# Voeding.net
KiCad netlist of a schematic drawn in Altium Designer
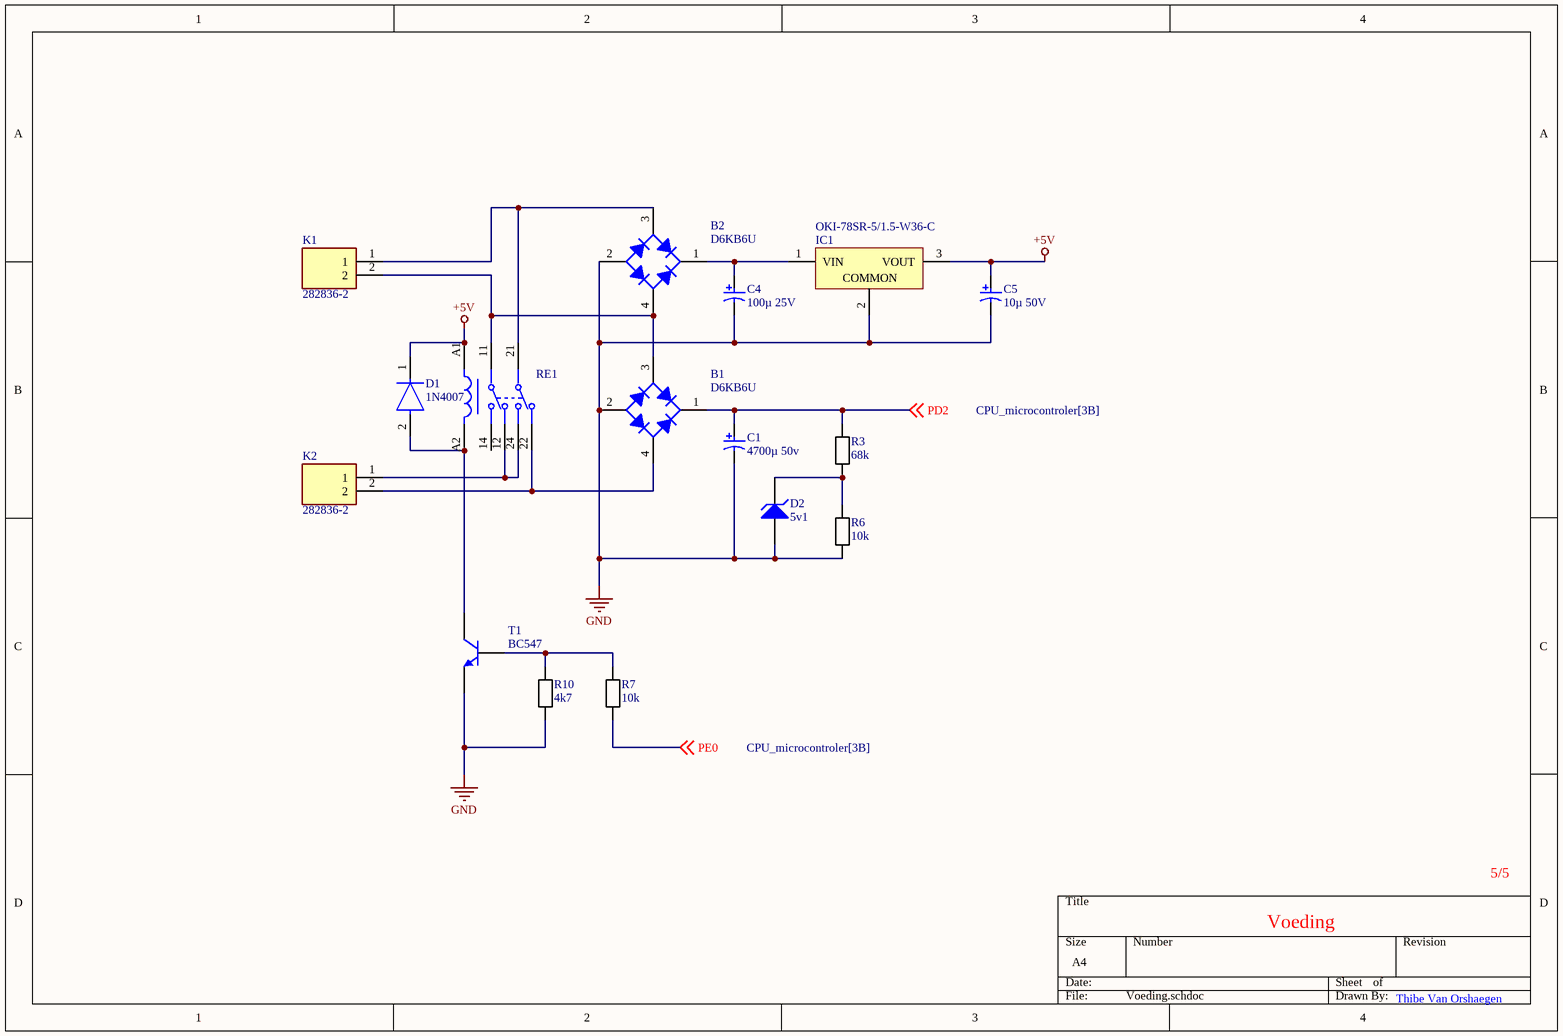
[diagram p0: Voeding.schdoc]

(export (version "E")
  (design (tool "Eeschema 10.0.6"))
  (components
    (comp (ref "B1")
      (value "D6KB6U")
      (footprint "ttf")
      (fields (field (name "MANUFACTURER") "Diodes Inc"))
      (libsource (lib "Soldeerstation") (part "Bridge_Rectifier"))
    )
    (comp (ref "B2")
      (value "D6KB6U")
      (footprint "ttf")
      (fields (field (name "MANUFACTURER") "Diodes Inc"))
      (libsource (lib "Soldeerstation") (part "Bridge_Rectifier"))
    )
    (comp (ref "C1")
      (value "4700µ 50v")
      (footprint "CE_D25_L25_plugin")
      (fields (field (name "MANUFACTURER") "Panasonic"))
      (libsource (lib "Soldeerstation") (part "Capacitor_Electrolytic"))
    )
    (comp (ref "C4")
      (value "100µ 25V")
      (footprint "CE_D8_L10")
      (fields (field (name "MANUFACTURER") "Panasonic"))
      (libsource (lib "Soldeerstation") (part "Capacitor_Electrolytic"))
    )
    (comp (ref "C5")
      (value "10µ 50V")
      (footprint "CE_D8_L10")
      (fields (field (name "MANUFACTURER") "Panasonic"))
      (libsource (lib "Soldeerstation") (part "Capacitor_Electrolytic"))
    )
    (comp (ref "D1")
      (value "1N4007")
      (footprint "SOD-123FL")
      (fields
        (field (name "MANUFACTURER") "Diotec")
        (field (name "OCTOPART") "https://octopart.com/1n4007-diotec-4040411")
      )
      (libsource (lib "Soldeerstation") (part "Diode"))
    )
    (comp (ref "D2")
      (value "5v1")
      (footprint "SOD-123FL")
      (fields (field (name "MANUFACTURER") "On Semiconductor") (field (name "PARTNUMBER") "1SMB5920BT3G"))
      (libsource (lib "Soldeerstation") (part "Zener_Diode"))
    )
    (comp (ref "IC1")
      (value "OKI-78SR-5/1.5-W36-C")
      (footprint "OKI78SR515W36C")
      (fields (field (name "MANUFACTURER") "Murata"))
      (libsource (lib "Soldeerstation") (part "DC/DC Converter"))
    )
    (comp (ref "K1")
      (value "282836-2")
      (footprint "PcbLib3:Schroefconnector 2 Pin")
      (description "Connector")
      (libsource (lib "Soldeerstation") (part "Schroefconnector 2 Pin L"))
    )
    (comp (ref "K2")
      (value "282836-2")
      (footprint "PcbLib3:Schroefconnector 2 Pin")
      (description "Connector")
      (libsource (lib "Soldeerstation") (part "Schroefconnector 2 Pin L"))
    )
    (comp (ref "R3")
      (value "68k")
      (footprint "RESC2013X50X30ML20T20")
      (fields (field (name "MANUFACTURER") "Vishay Dale") (field (name "PART NUMBER") "CRCW08050000Z0EA"))
      (libsource (lib "Soldeerstation") (part "Weerstand"))
    )
    (comp (ref "R6")
      (value "10k")
      (footprint "RESC2013X50X30ML20T20")
      (fields (field (name "MANUFACTURER") "Vishay Dale") (field (name "PART NUMBER") "CRCW08050000Z0EA"))
      (libsource (lib "Soldeerstation") (part "Weerstand"))
    )
    (comp (ref "R7")
      (value "10k")
      (footprint "RESC2013X50X30ML20T20")
      (fields (field (name "MANUFACTURER") "Vishay Dale") (field (name "PART NUMBER") "CRCW08050000Z0EA"))
      (libsource (lib "Soldeerstation") (part "Weerstand"))
    )
    (comp (ref "R10")
      (value "4k7")
      (footprint "RESC2013X50X30ML20T20")
      (fields (field (name "MANUFACTURER") "Vishay Dale") (field (name "PART NUMBER") "CRCW08050000Z0EA"))
      (libsource (lib "Soldeerstation") (part "Weerstand"))
    )
    (comp (ref "RE1")
      (value "~")
      (footprint "RT42")
      (fields
        (field (name "MANUFACTURER PART NUMBER") "RT424005")
        (field (name "OCTOPART") "https://octopart.com/5-1393243-9-te+connectivity-41835766")
        (field (name "MANUFACTURER") "TE Connectivity")
      )
      (libsource (lib "Soldeerstation") (part "RELAY_GENERAL_PURPOSE"))
    )
    (comp (ref "T1")
      (value "BC547")
      (footprint "SOT_23")
      (fields (field (name "MANUFACTURER") "On Semiconductor") (field (name "PARTNUMBER") "BC547C"))
      (libsource (lib "Soldeerstation") (part "Transistor_NPN"))
    )
  )
  (nets
    (net (code "1") (name "+5V") (class "Default")
      (node (ref "C5") (pin "2") (pinfunction "2_2") (pintype "passive"))
      (node (ref "D1") (pin "1") (pinfunction "C_1") (pintype "passive"))
      (node (ref "IC1") (pin "3") (pinfunction "VOUT_3") (pintype "power_in"))
      (node (ref "RE1") (pin "A1") (pinfunction "A1_A1") (pintype "passive"))
    )
    (net (code "2") (name "GND") (class "Default")
      (node (ref "B1") (pin "2") (pinfunction "A_2") (pintype "passive"))
      (node (ref "B2") (pin "2") (pinfunction "A_2") (pintype "passive"))
      (node (ref "C1") (pin "1") (pinfunction "1_1") (pintype "passive"))
      (node (ref "C4") (pin "1") (pinfunction "1_1") (pintype "passive"))
      (node (ref "C5") (pin "1") (pinfunction "1_1") (pintype "passive"))
      (node (ref "D2") (pin "2") (pinfunction "A_2") (pintype "passive"))
      (node (ref "IC1") (pin "2") (pinfunction "COMMON_2") (pintype "power_in"))
      (node (ref "R10") (pin "1") (pinfunction "1_1") (pintype "passive"))
      (node (ref "R6") (pin "1") (pinfunction "1_1") (pintype "passive"))
      (node (ref "T1") (pin "3") (pinfunction "E_3") (pintype "passive"))
    )
    (net (code "3") (name "Net-(B1-C-Pad3)") (class "Default")
      (node (ref "B1") (pin "3") (pinfunction "C_3") (pintype "passive"))
      (node (ref "B2") (pin "4") (pinfunction "C_4") (pintype "passive"))
      (node (ref "K1") (pin "2") (pinfunction "2_2") (pintype "passive"))
      (node (ref "RE1") (pin "11") (pinfunction "11_11") (pintype "passive"))
    )
    (net (code "4") (name "Net-(B1-C-Pad4)") (class "Default")
      (node (ref "B1") (pin "4") (pinfunction "C_4") (pintype "passive"))
      (node (ref "K2") (pin "2") (pinfunction "2_2") (pintype "passive"))
      (node (ref "RE1") (pin "22") (pinfunction "22_22") (pintype "passive"))
    )
    (net (code "5") (name "Net-(B2-C-Pad3)") (class "Default")
      (node (ref "B2") (pin "3") (pinfunction "C_3") (pintype "passive"))
      (node (ref "K1") (pin "1") (pinfunction "1_1") (pintype "passive"))
      (node (ref "RE1") (pin "21") (pinfunction "21_21") (pintype "passive"))
    )
    (net (code "6") (name "Net-(B2-K)") (class "Default")
      (node (ref "B2") (pin "1") (pinfunction "K_1") (pintype "passive"))
      (node (ref "C4") (pin "2") (pinfunction "2_2") (pintype "passive"))
      (node (ref "IC1") (pin "1") (pinfunction "VIN_1") (pintype "power_in"))
    )
    (net (code "7") (name "Net-(D1-A)") (class "Default")
      (node (ref "D1") (pin "2") (pinfunction "A_2") (pintype "passive"))
      (node (ref "RE1") (pin "A2") (pinfunction "A2_A2") (pintype "passive"))
      (node (ref "T1") (pin "1") (pinfunction "C_1") (pintype "passive"))
    )
    (net (code "8") (name "Net-(D2-K)") (class "Default")
      (node (ref "D2") (pin "1") (pinfunction "K_1") (pintype "passive"))
      (node (ref "R3") (pin "1") (pinfunction "1_1") (pintype "passive"))
      (node (ref "R6") (pin "2") (pinfunction "2_2") (pintype "passive"))
    )
    (net (code "9") (name "Net-(K2-Pad1)") (class "Default")
      (node (ref "K2") (pin "1") (pinfunction "1_1") (pintype "passive"))
      (node (ref "RE1") (pin "12") (pinfunction "12_12") (pintype "passive"))
      (node (ref "RE1") (pin "24") (pinfunction "24_24") (pintype "passive"))
    )
    (net (code "10") (name "Net-(T1-B)") (class "Default")
      (node (ref "R10") (pin "2") (pinfunction "2_2") (pintype "passive"))
      (node (ref "R7") (pin "2") (pinfunction "2_2") (pintype "passive"))
      (node (ref "T1") (pin "2") (pinfunction "B_2") (pintype "passive"))
    )
    (net (code "11") (name "PD2") (class "Default")
      (node (ref "B1") (pin "1") (pinfunction "K_1") (pintype "passive"))
      (node (ref "C1") (pin "2") (pinfunction "2_2") (pintype "passive"))
      (node (ref "R3") (pin "2") (pinfunction "2_2") (pintype "passive"))
    )
    (net (code "12") (name "PE0") (class "Default")
      (node (ref "R7") (pin "1") (pinfunction "1_1") (pintype "passive"))
    )
    (net (code "13") (name "unconnected-(RE1-Pad14)") (class "Default")
      (node (ref "RE1") (pin "14") (pinfunction "14_14") (pintype "passive"))
    )
  )
)
